# Dummy_load_schematic.net
KiCad netlist of a schematic drawn in EAGLE
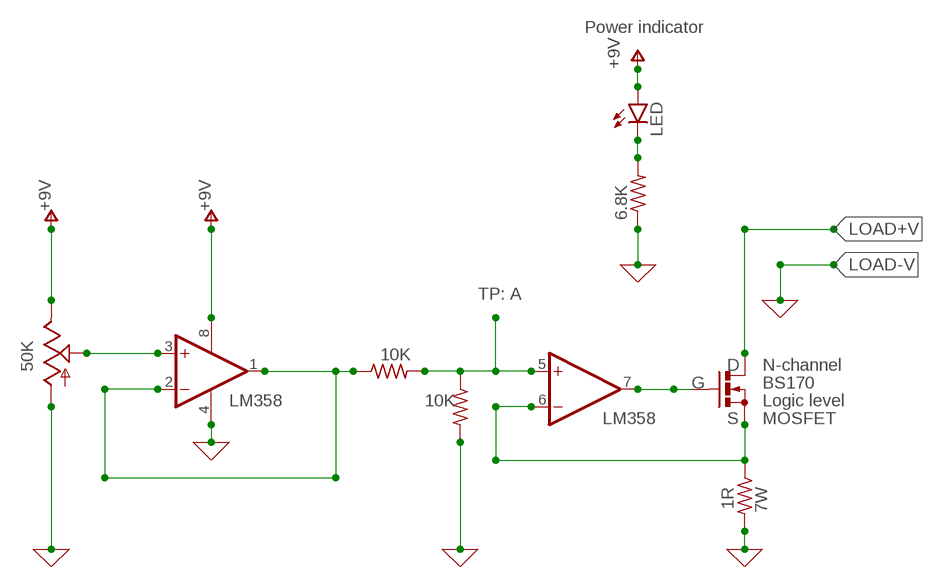
[diagram p0: schematic, sheet 1]

(export (version "E")
  (design (tool "Eeschema 10.0.6"))
  (components
    (comp (ref "6.8K")
      (value "R-US_0207/7")
      (footprint "eagle-import:0207_7")
      (libsource (lib "eagle-import") (part "R-US_0207/7"))
    )
    (comp (ref "7W")
      (value "1R")
      (footprint "eagle-import:0207_7")
      (libsource (lib "eagle-import") (part "R-US_0207/7"))
    )
    (comp (ref "10K")
      (value "R-US_0207/7")
      (footprint "eagle-import:0207_7")
      (libsource (lib "eagle-import") (part "R-US_0207/7"))
    )
    (comp (ref "50K")
      (value "50K")
      (footprint "eagle-import:EVUE")
      (libsource (lib "eagle-import") (part "US-EVUE2A"))
    )
    (comp (ref "LED")
      (value "LED5MM")
      (footprint "eagle-import:LED5MM")
      (libsource (lib "eagle-import") (part "LED5MM"))
    )
    (comp (ref "LM358")
      (value "LM358")
      (footprint "eagle-import:SOIC8")
      (libsource (lib "eagle-import") (part "OP1277R"))
    )
    (comp (ref "N-CHANNEL")
      (value "BS170")
      (footprint "eagle-import:SOT54E")
      (libsource (lib "eagle-import") (part "BS170"))
    )
    (comp (ref "R3")
      (value "10K")
      (footprint "eagle-import:0207_7")
      (libsource (lib "eagle-import") (part "R-US_0207/7"))
    )
  )
  (nets
    (net (code "1") (name "+9V") (class "Default")
      (node (ref "50K") (pin "3") (pinfunction "E_3") (pintype "passive"))
      (node (ref "LED") (pin "A") (pinfunction "A_A") (pintype "passive"))
      (node (ref "LM358") (pin "8") (pinfunction "V+_8") (pintype "power_in"))
    )
    (net (code "2") (name "LOAD+V") (class "Default")
      (node (ref "N-CHANNEL") (pin "D") (pinfunction "D_D") (pintype "passive"))
    )
    (net (code "3") (name "LOAD-V") (class "Default")
      (node (ref "50K") (pin "1") (pinfunction "A_1") (pintype "passive"))
      (node (ref "6.8K") (pin "1") (pinfunction "1_1") (pintype "passive"))
      (node (ref "7W") (pin "2") (pinfunction "2_2") (pintype "passive"))
      (node (ref "LM358") (pin "4") (pinfunction "V-_4") (pintype "power_in"))
      (node (ref "R3") (pin "2") (pinfunction "2_2") (pintype "passive"))
    )
    (net (code "4") (name "Net-(50K-S)") (class "Default")
      (node (ref "50K") (pin "2") (pinfunction "S_2") (pintype "passive"))
      (node (ref "LM358") (pin "3") (pinfunction "+IN_3") (pintype "input"))
    )
    (net (code "5") (name "Net-(LED-C)") (class "Default")
      (node (ref "6.8K") (pin "2") (pinfunction "2_2") (pintype "passive"))
      (node (ref "LED") (pin "K") (pinfunction "C_K") (pintype "passive"))
    )
    (net (code "6") (name "Net-(LM358A--IN)") (class "Default")
      (node (ref "10K") (pin "1") (pinfunction "1_1") (pintype "passive"))
      (node (ref "LM358") (pin "1") (pinfunction "OUT_1") (pintype "output"))
      (node (ref "LM358") (pin "2") (pinfunction "-IN_2") (pintype "input"))
    )
    (net (code "7") (name "Net-(LM358B-+IN)") (class "Default")
      (node (ref "10K") (pin "2") (pinfunction "2_2") (pintype "passive"))
      (node (ref "LM358") (pin "5") (pinfunction "+IN_5") (pintype "input"))
      (node (ref "R3") (pin "1") (pinfunction "1_1") (pintype "passive"))
    )
    (net (code "8") (name "Net-(LM358B--IN)") (class "Default")
      (node (ref "7W") (pin "1") (pinfunction "1_1") (pintype "passive"))
      (node (ref "LM358") (pin "6") (pinfunction "-IN_6") (pintype "input"))
      (node (ref "N-CHANNEL") (pin "S") (pinfunction "S_S") (pintype "passive"))
    )
    (net (code "9") (name "Net-(LM358B-OUT)") (class "Default")
      (node (ref "LM358") (pin "7") (pinfunction "OUT_7") (pintype "output"))
      (node (ref "N-CHANNEL") (pin "G") (pinfunction "G_G") (pintype "passive"))
    )
  )
)
